# 05-_-.net
KiCad netlist of a schematic drawn in Altium Designer
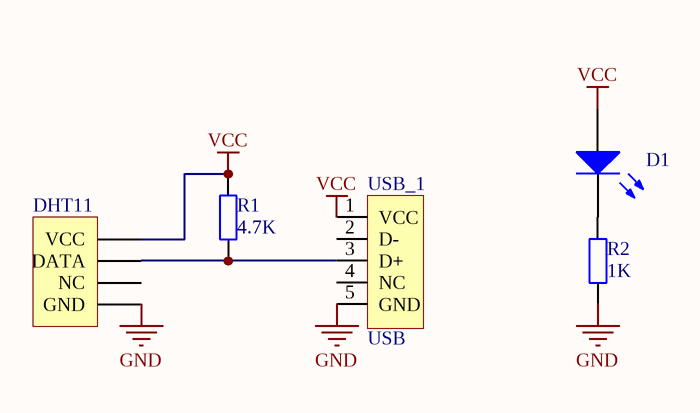
[diagram p0: 05-温湿度传感器模块-原理图.SchDoc]

(export (version "E")
  (design (tool "Eeschema 10.0.6"))
  (components
    (comp (ref "D1")
      (value "LED0")
      (footprint "0805")
      (description "Typical INFRARED GaAs LED")
      (fields (field (name "PUBLISHER") "Altium Limited"))
      (libsource (lib "Miscellaneous Devices") (part "LED0"))
    )
    (comp (ref "DHT11")
      (value "Header 4")
      (footprint "DHT11")
      (description "Header, 4-Pin")
      (fields (field (name "PUBLISHER") "Altium Limited"))
      (libsource (lib "Miscellaneous Connectors") (part "Header 4"))
    )
    (comp (ref "R1")
      (value "4.7K")
      (footprint "0805")
      (description "Resistor")
      (fields (field (name "Comment") "Res2") (field (name "PUBLISHER") "Altium Limited"))
      (libsource (lib "Miscellaneous Devices") (part "Res2"))
    )
    (comp (ref "R2")
      (value "1K")
      (footprint "0805")
      (description "Resistor")
      (fields (field (name "Comment") "Res2") (field (name "PUBLISHER") "Altium Limited"))
      (libsource (lib "Miscellaneous Devices") (part "Res2"))
    )
    (comp (ref "USB_1") (value "USB") (footprint "USB/SM0.8-6H5") (libsource (lib "原理图库") (part "USB5")))
  )
  (nets
    (net (code "1") (name "GND") (class "Default")
      (node (ref "DHT11") (pin "4") (pinfunction "GND_4") (pintype "passive"))
      (node (ref "R2") (pin "1") (pinfunction "1_1") (pintype "passive"))
      (node (ref "USB_1") (pin "5") (pinfunction "GND_5") (pintype "passive"))
    )
    (net (code "2") (name "Net-(D1-K)") (class "Default")
      (node (ref "D1") (pin "2") (pinfunction "K_2") (pintype "passive"))
      (node (ref "R2") (pin "2") (pinfunction "2_2") (pintype "passive"))
    )
    (net (code "3") (name "Net-(DHT11-DATA)") (class "Default")
      (node (ref "DHT11") (pin "2") (pinfunction "DATA_2") (pintype "passive"))
      (node (ref "R1") (pin "1") (pinfunction "1_1") (pintype "passive"))
      (node (ref "USB_1") (pin "3") (pinfunction "D+_3") (pintype "passive"))
    )
    (net (code "4") (name "VCC") (class "Default")
      (node (ref "D1") (pin "1") (pinfunction "A_1") (pintype "passive"))
      (node (ref "DHT11") (pin "1") (pinfunction "VCC_1") (pintype "passive"))
      (node (ref "R1") (pin "2") (pinfunction "2_2") (pintype "passive"))
      (node (ref "USB_1") (pin "1") (pinfunction "VCC_1") (pintype "passive"))
    )
    (net (code "5") (name "unconnected-(DHT11-NC-Pad3)") (class "Default")
      (node (ref "DHT11") (pin "3") (pinfunction "NC_3") (pintype "passive"))
    )
    (net (code "6") (name "unconnected-(USB_1-D--Pad2)") (class "Default")
      (node (ref "USB_1") (pin "2") (pinfunction "D-_2") (pintype "passive"))
    )
    (net (code "7") (name "unconnected-(USB_1-NC-Pad4)") (class "Default")
      (node (ref "USB_1") (pin "4") (pinfunction "NC_4") (pintype "passive"))
    )
  )
)
